# node_V1.net
KiCad netlist of a schematic drawn in EAGLE
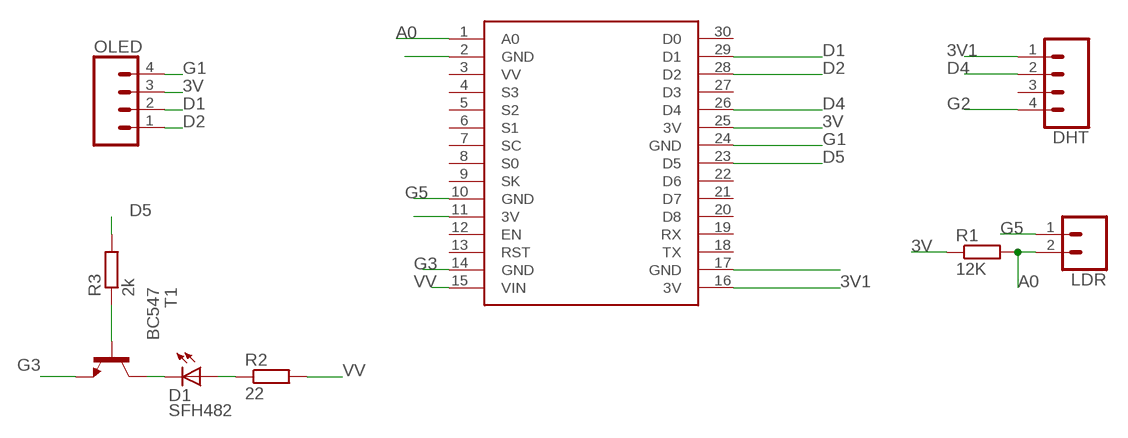
[diagram p0: schematic, sheet 1]

(export (version "E")
  (design (tool "Eeschema 10.0.6"))
  (components
    (comp (ref "D1")
      (value "SFH482")
      (footprint "eagle-import:SFH482")
      (libsource (lib "eagle-import") (part "SFH482"))
    )
    (comp (ref "DHT")
      (value "CONN_04LONGPADS")
      (footprint "eagle-import:1X04_LONGPADS")
      (libsource (lib "eagle-import") (part "CONN_04LONGPADS"))
    )
    (comp (ref "LDR")
      (value "CONN_02PTH3")
      (footprint "eagle-import:1X02_LONGPADS")
      (libsource (lib "eagle-import") (part "CONN_02PTH3"))
    )
    (comp (ref "OLED")
      (value "CONN_04LONGPADS")
      (footprint "eagle-import:1X04_LONGPADS")
      (libsource (lib "eagle-import") (part "CONN_04LONGPADS"))
    )
    (comp (ref "R1")
      (value "12K")
      (footprint "eagle-import:0207_10")
      (libsource (lib "eagle-import") (part "R-EU_0207/10"))
    )
    (comp (ref "R2")
      (value "22")
      (footprint "eagle-import:0207_10")
      (libsource (lib "eagle-import") (part "R-EU_0207/10"))
    )
    (comp (ref "R3")
      (value "2k")
      (footprint "eagle-import:0207_10")
      (libsource (lib "eagle-import") (part "R-EU_0207/10"))
    )
    (comp (ref "T1")
      (value "BC547")
      (footprint "eagle-import:TO92")
      (libsource (lib "eagle-import") (part "BC547"))
    )
    (comp (ref "U$2")
      (value "NODEMCU")
      (footprint "eagle-import:NODEMCU")
      (libsource (lib "eagle-import") (part "NODEMCU"))
    )
  )
  (nets
    (net (code "1") (name "/3V") (class "Default")
      (node (ref "OLED") (pin "3") (pinfunction "3_3") (pintype "passive"))
      (node (ref "R1") (pin "1") (pinfunction "1_1") (pintype "passive"))
      (node (ref "U$2") (pin "25") (pinfunction "3V_25") (pintype "power_in"))
    )
    (net (code "2") (name "/3V1") (class "Default")
      (node (ref "DHT") (pin "1") (pinfunction "1_1") (pintype "passive"))
      (node (ref "U$2") (pin "16") (pinfunction "3V_16") (pintype "power_in"))
    )
    (net (code "3") (name "/A0") (class "Default")
      (node (ref "LDR") (pin "2") (pinfunction "2_2") (pintype "passive"))
      (node (ref "R1") (pin "2") (pinfunction "2_2") (pintype "passive"))
      (node (ref "U$2") (pin "1") (pinfunction "A0_1") (pintype "bidirectional"))
    )
    (net (code "4") (name "/D1") (class "Default")
      (node (ref "OLED") (pin "2") (pinfunction "2_2") (pintype "passive"))
      (node (ref "U$2") (pin "29") (pinfunction "D1_29") (pintype "bidirectional"))
    )
    (net (code "5") (name "/D2") (class "Default")
      (node (ref "OLED") (pin "1") (pinfunction "1_1") (pintype "passive"))
      (node (ref "U$2") (pin "28") (pinfunction "D2_28") (pintype "bidirectional"))
    )
    (net (code "6") (name "/D4") (class "Default")
      (node (ref "DHT") (pin "2") (pinfunction "2_2") (pintype "passive"))
      (node (ref "U$2") (pin "26") (pinfunction "D4_26") (pintype "bidirectional"))
    )
    (net (code "7") (name "/D5") (class "Default")
      (node (ref "R3") (pin "2") (pinfunction "2_2") (pintype "passive"))
      (node (ref "U$2") (pin "23") (pinfunction "D5_23") (pintype "bidirectional"))
    )
    (net (code "8") (name "/G1") (class "Default")
      (node (ref "OLED") (pin "4") (pinfunction "4_4") (pintype "passive"))
      (node (ref "U$2") (pin "24") (pinfunction "GND_24") (pintype "power_in"))
    )
    (net (code "9") (name "/G2") (class "Default")
      (node (ref "DHT") (pin "4") (pinfunction "4_4") (pintype "passive"))
      (node (ref "U$2") (pin "17") (pinfunction "GND_17") (pintype "power_in"))
    )
    (net (code "10") (name "/G3") (class "Default")
      (node (ref "T1") (pin "1") (pinfunction "E_1") (pintype "passive"))
      (node (ref "U$2") (pin "14") (pinfunction "GND_14") (pintype "power_in"))
    )
    (net (code "11") (name "/G5") (class "Default")
      (node (ref "LDR") (pin "1") (pinfunction "1_1") (pintype "passive"))
      (node (ref "U$2") (pin "10") (pinfunction "GND_10") (pintype "power_in"))
      (node (ref "U$2") (pin "2") (pinfunction "GND_2") (pintype "power_in"))
    )
    (net (code "12") (name "/VV") (class "Default")
      (node (ref "R2") (pin "2") (pinfunction "2_2") (pintype "passive"))
      (node (ref "U$2") (pin "15") (pinfunction "VIN_15") (pintype "bidirectional"))
    )
    (net (code "13") (name "Net-(D1-C)") (class "Default")
      (node (ref "D1") (pin "K") (pinfunction "C_K") (pintype "passive"))
      (node (ref "T1") (pin "3") (pinfunction "C_3") (pintype "passive"))
    )
    (net (code "14") (name "Net-(D1-PadA)") (class "Default")
      (node (ref "D1") (pin "A") (pinfunction "A_A") (pintype "passive"))
      (node (ref "R2") (pin "1") (pinfunction "1_1") (pintype "passive"))
    )
    (net (code "15") (name "Net-(T1-B)") (class "Default")
      (node (ref "R3") (pin "1") (pinfunction "1_1") (pintype "passive"))
      (node (ref "T1") (pin "2") (pinfunction "B_2") (pintype "passive"))
    )
    (net (code "16") (name "unconnected-(DHT-Pad3)") (class "Default")
      (node (ref "DHT") (pin "3") (pinfunction "3_3") (pintype "passive"))
    )
    (net (code "17") (name "unconnected-(U$2-3V-Pad11)") (class "Default")
      (node (ref "U$2") (pin "11") (pinfunction "3V_11") (pintype "power_in"))
    )
    (net (code "18") (name "unconnected-(U$2-D0-Pad30)") (class "Default")
      (node (ref "U$2") (pin "30") (pinfunction "D0_30") (pintype "bidirectional"))
    )
    (net (code "19") (name "unconnected-(U$2-D3-Pad27)") (class "Default")
      (node (ref "U$2") (pin "27") (pinfunction "D3_27") (pintype "bidirectional"))
    )
    (net (code "20") (name "unconnected-(U$2-D6-Pad22)") (class "Default")
      (node (ref "U$2") (pin "22") (pinfunction "D6_22") (pintype "bidirectional"))
    )
    (net (code "21") (name "unconnected-(U$2-D7-Pad21)") (class "Default")
      (node (ref "U$2") (pin "21") (pinfunction "D7_21") (pintype "bidirectional"))
    )
    (net (code "22") (name "unconnected-(U$2-D8-Pad20)") (class "Default")
      (node (ref "U$2") (pin "20") (pinfunction "D8_20") (pintype "bidirectional"))
    )
    (net (code "23") (name "unconnected-(U$2-EN-Pad12)") (class "Default")
      (node (ref "U$2") (pin "12") (pinfunction "EN_12") (pintype "bidirectional"))
    )
    (net (code "24") (name "unconnected-(U$2-RST-Pad13)") (class "Default")
      (node (ref "U$2") (pin "13") (pinfunction "RST_13") (pintype "bidirectional"))
    )
    (net (code "25") (name "unconnected-(U$2-RX-Pad19)") (class "Default")
      (node (ref "U$2") (pin "19") (pinfunction "RX_19") (pintype "bidirectional"))
    )
    (net (code "26") (name "unconnected-(U$2-S0-Pad8)") (class "Default")
      (node (ref "U$2") (pin "8") (pinfunction "S0_8") (pintype "bidirectional"))
    )
    (net (code "27") (name "unconnected-(U$2-S1-Pad6)") (class "Default")
      (node (ref "U$2") (pin "6") (pinfunction "S1_6") (pintype "bidirectional"))
    )
    (net (code "28") (name "unconnected-(U$2-S2-Pad5)") (class "Default")
      (node (ref "U$2") (pin "5") (pinfunction "S2_5") (pintype "bidirectional"))
    )
    (net (code "29") (name "unconnected-(U$2-S3-Pad4)") (class "Default")
      (node (ref "U$2") (pin "4") (pinfunction "S3_4") (pintype "bidirectional"))
    )
    (net (code "30") (name "unconnected-(U$2-SC-Pad7)") (class "Default")
      (node (ref "U$2") (pin "7") (pinfunction "SC_7") (pintype "bidirectional"))
    )
    (net (code "31") (name "unconnected-(U$2-SK-Pad9)") (class "Default")
      (node (ref "U$2") (pin "9") (pinfunction "SK_9") (pintype "bidirectional"))
    )
    (net (code "32") (name "unconnected-(U$2-TX-Pad18)") (class "Default")
      (node (ref "U$2") (pin "18") (pinfunction "TX_18") (pintype "bidirectional"))
    )
    (net (code "33") (name "unconnected-(U$2-VV-Pad3)") (class "Default")
      (node (ref "U$2") (pin "3") (pinfunction "VV_3") (pintype "bidirectional"))
    )
  )
)
